# Xmas_Tree.net
KiCad netlist of a schematic drawn in EAGLE
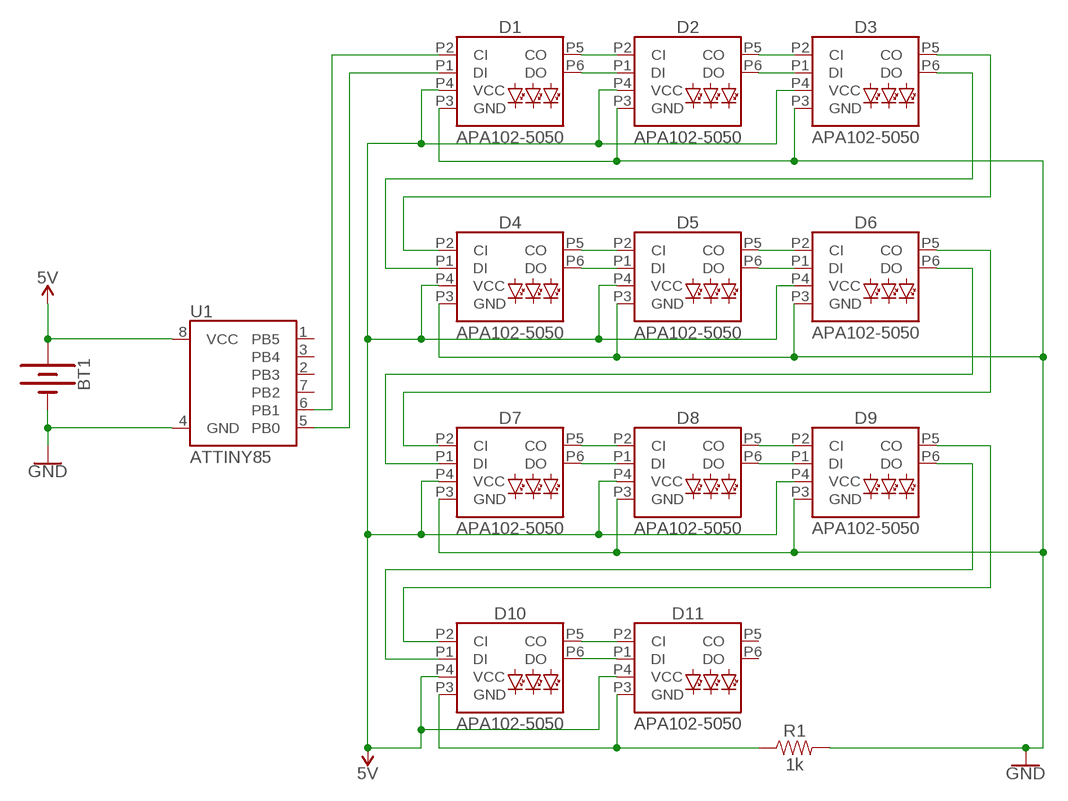
[diagram p0: schematic, sheet 1]

(export (version "E")
  (design (tool "Eeschema 10.0.6"))
  (components
    (comp (ref "BT1")
      (value "BATTERY-20MM_PTH")
      (footprint "eagle-import:BATTCOM_20MM_PTH")
      (libsource (lib "eagle-import") (part "BATTERY-20MM_PTH"))
    )
    (comp (ref "D1")
      (value "APA102-5050")
      (footprint "eagle-import:APA102-5050")
      (libsource (lib "eagle-import") (part "APA102-5050"))
    )
    (comp (ref "D2")
      (value "APA102-5050")
      (footprint "eagle-import:APA102-5050")
      (libsource (lib "eagle-import") (part "APA102-5050"))
    )
    (comp (ref "D3")
      (value "APA102-5050")
      (footprint "eagle-import:APA102-5050")
      (libsource (lib "eagle-import") (part "APA102-5050"))
    )
    (comp (ref "D4")
      (value "APA102-5050")
      (footprint "eagle-import:APA102-5050")
      (libsource (lib "eagle-import") (part "APA102-5050"))
    )
    (comp (ref "D5")
      (value "APA102-5050")
      (footprint "eagle-import:APA102-5050")
      (libsource (lib "eagle-import") (part "APA102-5050"))
    )
    (comp (ref "D6")
      (value "APA102-5050")
      (footprint "eagle-import:APA102-5050")
      (libsource (lib "eagle-import") (part "APA102-5050"))
    )
    (comp (ref "D7")
      (value "APA102-5050")
      (footprint "eagle-import:APA102-5050")
      (libsource (lib "eagle-import") (part "APA102-5050"))
    )
    (comp (ref "D8")
      (value "APA102-5050")
      (footprint "eagle-import:APA102-5050")
      (libsource (lib "eagle-import") (part "APA102-5050"))
    )
    (comp (ref "D9")
      (value "APA102-5050")
      (footprint "eagle-import:APA102-5050")
      (libsource (lib "eagle-import") (part "APA102-5050"))
    )
    (comp (ref "D10")
      (value "APA102-5050")
      (footprint "eagle-import:APA102-5050")
      (libsource (lib "eagle-import") (part "APA102-5050"))
    )
    (comp (ref "D11")
      (value "APA102-5050")
      (footprint "eagle-import:APA102-5050")
      (libsource (lib "eagle-import") (part "APA102-5050"))
    )
    (comp (ref "R1")
      (value "1k")
      (footprint "eagle-import:0603")
      (libsource (lib "eagle-import") (part "1KOHM-0603-1/10W-1%"))
    )
    (comp (ref "U1")
      (value "ATTINY85")
      (footprint "eagle-import:ATTINY85")
      (libsource (lib "eagle-import") (part "ATTINY85"))
    )
  )
  (nets
    (net (code "1") (name "5V") (class "Default")
      (node (ref "BT1") (pin "1") (pinfunction "+_1") (pintype "power_in"))
      (node (ref "D1") (pin "P4") (pinfunction "VCC_P4") (pintype "bidirectional"))
      (node (ref "D10") (pin "P4") (pinfunction "VCC_P4") (pintype "bidirectional"))
      (node (ref "D11") (pin "P4") (pinfunction "VCC_P4") (pintype "bidirectional"))
      (node (ref "D2") (pin "P4") (pinfunction "VCC_P4") (pintype "bidirectional"))
      (node (ref "D3") (pin "P4") (pinfunction "VCC_P4") (pintype "bidirectional"))
      (node (ref "D4") (pin "P4") (pinfunction "VCC_P4") (pintype "bidirectional"))
      (node (ref "D5") (pin "P4") (pinfunction "VCC_P4") (pintype "bidirectional"))
      (node (ref "D6") (pin "P4") (pinfunction "VCC_P4") (pintype "bidirectional"))
      (node (ref "D7") (pin "P4") (pinfunction "VCC_P4") (pintype "bidirectional"))
      (node (ref "D8") (pin "P4") (pinfunction "VCC_P4") (pintype "bidirectional"))
      (node (ref "D9") (pin "P4") (pinfunction "VCC_P4") (pintype "bidirectional"))
      (node (ref "U1") (pin "8") (pinfunction "VCC_8") (pintype "bidirectional"))
    )
    (net (code "2") (name "GND") (class "Default")
      (node (ref "BT1") (pin "2") (pinfunction "-_2") (pintype "power_in"))
      (node (ref "D1") (pin "P3") (pinfunction "GND_P3") (pintype "bidirectional"))
      (node (ref "D10") (pin "P3") (pinfunction "GND_P3") (pintype "bidirectional"))
      (node (ref "D11") (pin "P3") (pinfunction "GND_P3") (pintype "bidirectional"))
      (node (ref "D2") (pin "P3") (pinfunction "GND_P3") (pintype "bidirectional"))
      (node (ref "D3") (pin "P3") (pinfunction "GND_P3") (pintype "bidirectional"))
      (node (ref "D4") (pin "P3") (pinfunction "GND_P3") (pintype "bidirectional"))
      (node (ref "D5") (pin "P3") (pinfunction "GND_P3") (pintype "bidirectional"))
      (node (ref "D6") (pin "P3") (pinfunction "GND_P3") (pintype "bidirectional"))
      (node (ref "D7") (pin "P3") (pinfunction "GND_P3") (pintype "bidirectional"))
      (node (ref "D8") (pin "P3") (pinfunction "GND_P3") (pintype "bidirectional"))
      (node (ref "D9") (pin "P3") (pinfunction "GND_P3") (pintype "bidirectional"))
      (node (ref "R1") (pin "1") (pinfunction "1_1") (pintype "passive"))
      (node (ref "R1") (pin "2") (pinfunction "2_2") (pintype "passive"))
      (node (ref "U1") (pin "4") (pinfunction "GND_4") (pintype "bidirectional"))
    )
    (net (code "3") (name "Net-(D1-CI)") (class "Default")
      (node (ref "D1") (pin "P2") (pinfunction "CI_P2") (pintype "bidirectional"))
      (node (ref "U1") (pin "6") (pinfunction "PB1_6") (pintype "bidirectional"))
    )
    (net (code "4") (name "Net-(D1-CO)") (class "Default")
      (node (ref "D1") (pin "P5") (pinfunction "CO_P5") (pintype "bidirectional"))
      (node (ref "D2") (pin "P2") (pinfunction "CI_P2") (pintype "bidirectional"))
    )
    (net (code "5") (name "Net-(D1-DI)") (class "Default")
      (node (ref "D1") (pin "P1") (pinfunction "DI_P1") (pintype "bidirectional"))
      (node (ref "U1") (pin "5") (pinfunction "PB0_5") (pintype "bidirectional"))
    )
    (net (code "6") (name "Net-(D1-DO)") (class "Default")
      (node (ref "D1") (pin "P6") (pinfunction "DO_P6") (pintype "bidirectional"))
      (node (ref "D2") (pin "P1") (pinfunction "DI_P1") (pintype "bidirectional"))
    )
    (net (code "7") (name "Net-(D2-CO)") (class "Default")
      (node (ref "D2") (pin "P5") (pinfunction "CO_P5") (pintype "bidirectional"))
      (node (ref "D3") (pin "P2") (pinfunction "CI_P2") (pintype "bidirectional"))
    )
    (net (code "8") (name "Net-(D2-DO)") (class "Default")
      (node (ref "D2") (pin "P6") (pinfunction "DO_P6") (pintype "bidirectional"))
      (node (ref "D3") (pin "P1") (pinfunction "DI_P1") (pintype "bidirectional"))
    )
    (net (code "9") (name "Net-(D3-CO)") (class "Default")
      (node (ref "D3") (pin "P5") (pinfunction "CO_P5") (pintype "bidirectional"))
      (node (ref "D4") (pin "P2") (pinfunction "CI_P2") (pintype "bidirectional"))
    )
    (net (code "10") (name "Net-(D3-DO)") (class "Default")
      (node (ref "D3") (pin "P6") (pinfunction "DO_P6") (pintype "bidirectional"))
      (node (ref "D4") (pin "P1") (pinfunction "DI_P1") (pintype "bidirectional"))
    )
    (net (code "11") (name "Net-(D4-CO)") (class "Default")
      (node (ref "D4") (pin "P5") (pinfunction "CO_P5") (pintype "bidirectional"))
      (node (ref "D5") (pin "P2") (pinfunction "CI_P2") (pintype "bidirectional"))
    )
    (net (code "12") (name "Net-(D4-DO)") (class "Default")
      (node (ref "D4") (pin "P6") (pinfunction "DO_P6") (pintype "bidirectional"))
      (node (ref "D5") (pin "P1") (pinfunction "DI_P1") (pintype "bidirectional"))
    )
    (net (code "13") (name "Net-(D5-CO)") (class "Default")
      (node (ref "D5") (pin "P5") (pinfunction "CO_P5") (pintype "bidirectional"))
      (node (ref "D6") (pin "P2") (pinfunction "CI_P2") (pintype "bidirectional"))
    )
    (net (code "14") (name "Net-(D5-DO)") (class "Default")
      (node (ref "D5") (pin "P6") (pinfunction "DO_P6") (pintype "bidirectional"))
      (node (ref "D6") (pin "P1") (pinfunction "DI_P1") (pintype "bidirectional"))
    )
    (net (code "15") (name "Net-(D6-CO)") (class "Default")
      (node (ref "D6") (pin "P5") (pinfunction "CO_P5") (pintype "bidirectional"))
      (node (ref "D7") (pin "P2") (pinfunction "CI_P2") (pintype "bidirectional"))
    )
    (net (code "16") (name "Net-(D6-DO)") (class "Default")
      (node (ref "D6") (pin "P6") (pinfunction "DO_P6") (pintype "bidirectional"))
      (node (ref "D7") (pin "P1") (pinfunction "DI_P1") (pintype "bidirectional"))
    )
    (net (code "17") (name "Net-(D7-CO)") (class "Default")
      (node (ref "D7") (pin "P5") (pinfunction "CO_P5") (pintype "bidirectional"))
      (node (ref "D8") (pin "P2") (pinfunction "CI_P2") (pintype "bidirectional"))
    )
    (net (code "18") (name "Net-(D7-DO)") (class "Default")
      (node (ref "D7") (pin "P6") (pinfunction "DO_P6") (pintype "bidirectional"))
      (node (ref "D8") (pin "P1") (pinfunction "DI_P1") (pintype "bidirectional"))
    )
    (net (code "19") (name "Net-(D8-CO)") (class "Default")
      (node (ref "D8") (pin "P5") (pinfunction "CO_P5") (pintype "bidirectional"))
      (node (ref "D9") (pin "P2") (pinfunction "CI_P2") (pintype "bidirectional"))
    )
    (net (code "20") (name "Net-(D8-DO)") (class "Default")
      (node (ref "D8") (pin "P6") (pinfunction "DO_P6") (pintype "bidirectional"))
      (node (ref "D9") (pin "P1") (pinfunction "DI_P1") (pintype "bidirectional"))
    )
    (net (code "21") (name "Net-(D10-CI)") (class "Default")
      (node (ref "D10") (pin "P2") (pinfunction "CI_P2") (pintype "bidirectional"))
      (node (ref "D9") (pin "P5") (pinfunction "CO_P5") (pintype "bidirectional"))
    )
    (net (code "22") (name "Net-(D10-CO)") (class "Default")
      (node (ref "D10") (pin "P5") (pinfunction "CO_P5") (pintype "bidirectional"))
      (node (ref "D11") (pin "P2") (pinfunction "CI_P2") (pintype "bidirectional"))
    )
    (net (code "23") (name "Net-(D10-DI)") (class "Default")
      (node (ref "D10") (pin "P1") (pinfunction "DI_P1") (pintype "bidirectional"))
      (node (ref "D9") (pin "P6") (pinfunction "DO_P6") (pintype "bidirectional"))
    )
    (net (code "24") (name "Net-(D10-DO)") (class "Default")
      (node (ref "D10") (pin "P6") (pinfunction "DO_P6") (pintype "bidirectional"))
      (node (ref "D11") (pin "P1") (pinfunction "DI_P1") (pintype "bidirectional"))
    )
    (net (code "25") (name "unconnected-(D11-CO-PadP5)") (class "Default")
      (node (ref "D11") (pin "P5") (pinfunction "CO_P5") (pintype "bidirectional"))
    )
    (net (code "26") (name "unconnected-(D11-DO-PadP6)") (class "Default")
      (node (ref "D11") (pin "P6") (pinfunction "DO_P6") (pintype "bidirectional"))
    )
    (net (code "27") (name "unconnected-(U1-PB2-Pad7)") (class "Default")
      (node (ref "U1") (pin "7") (pinfunction "PB2_7") (pintype "bidirectional"))
    )
    (net (code "28") (name "unconnected-(U1-PB3-Pad2)") (class "Default")
      (node (ref "U1") (pin "2") (pinfunction "PB3_2") (pintype "bidirectional"))
    )
    (net (code "29") (name "unconnected-(U1-PB4-Pad3)") (class "Default")
      (node (ref "U1") (pin "3") (pinfunction "PB4_3") (pintype "bidirectional"))
    )
    (net (code "30") (name "unconnected-(U1-PB5-Pad1)") (class "Default")
      (node (ref "U1") (pin "1") (pinfunction "PB5_1") (pintype "bidirectional"))
    )
  )
)
